# K210Module.net
KiCad netlist of a schematic drawn in Altium Designer
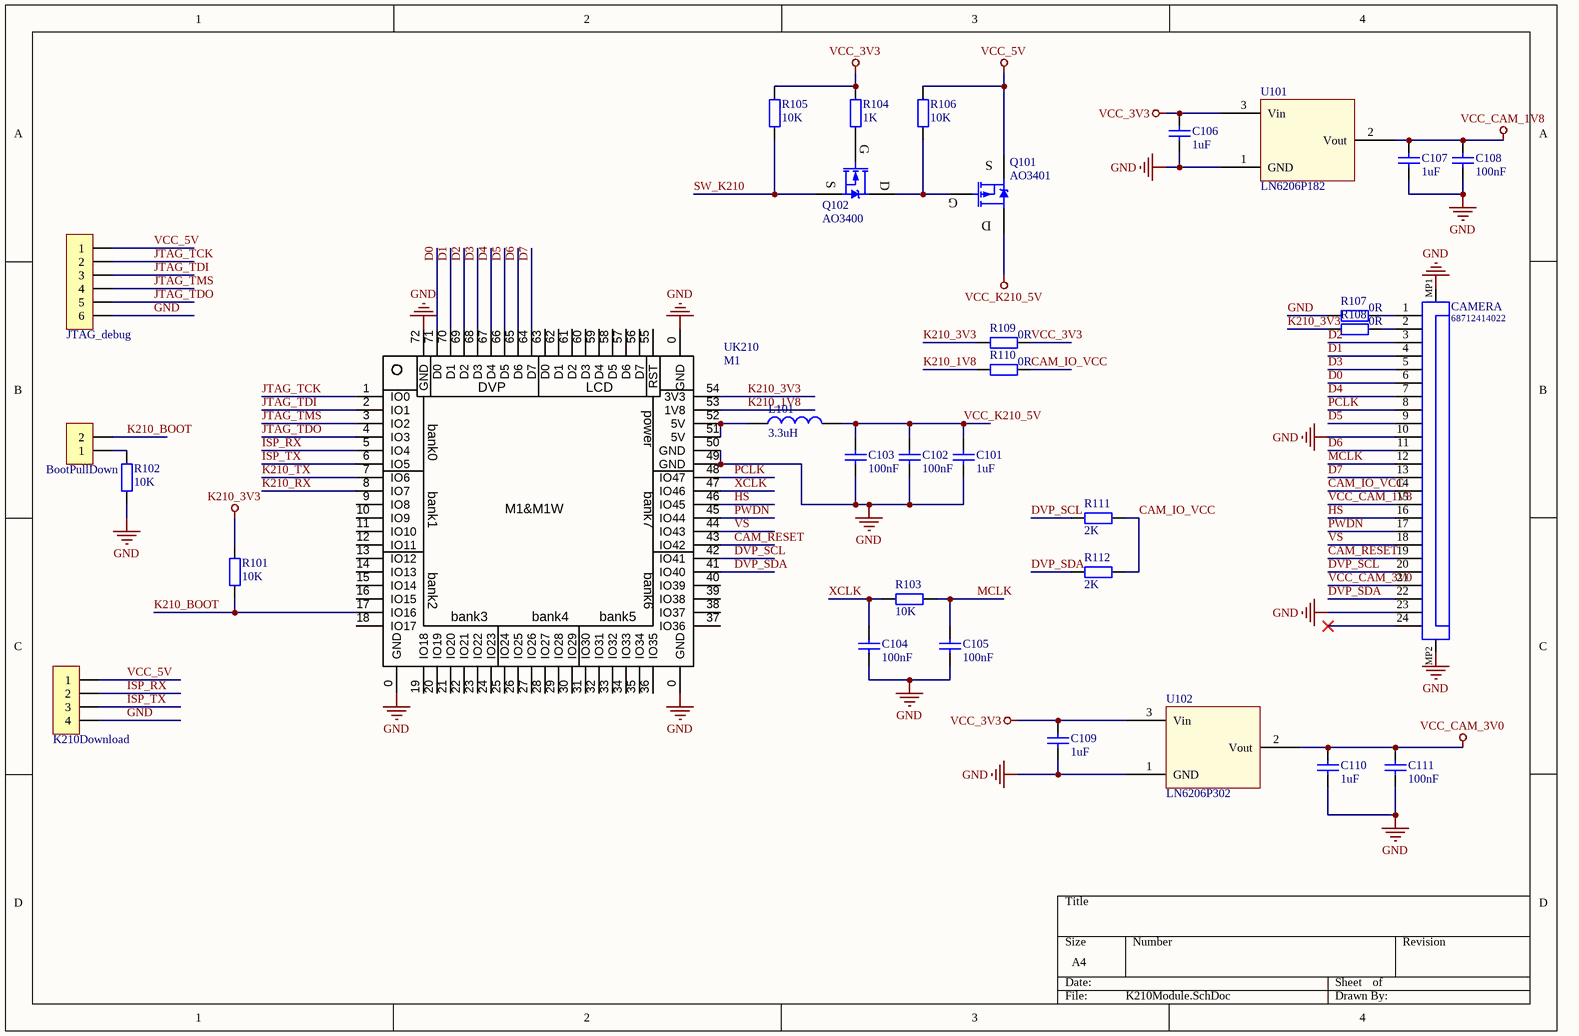
[diagram p0: K210Module.SchDoc]

(export (version "E")
  (design (tool "Eeschema 10.0.6"))
  (components
    (comp (ref "BootPullDown")
      (value "HDR-1X2")
      (footprint "HDR2.54-LI-2P")
      (description "2P接插件")
      (libsource (lib "5.5 - 2.54mm连接器(KF2EDGK_XH2.54_2.54排针排母)") (part "Header 2"))
    )
    (comp (ref "C101")
      (value "1uF")
      (footprint "C0603_L")
      (description "贴片电容/MLCC电容")
      (libsource (lib "0.1 - 电阻-电容-电感-晶振-晶体-磁珠-电位器-法拉电容-馈通电容") (part "C"))
    )
    (comp (ref "C102")
      (value "100nF")
      (footprint "C0603_L")
      (description "贴片电容/MLCC电容")
      (libsource (lib "0.1 - 电阻-电容-电感-晶振-晶体-磁珠-电位器-法拉电容-馈通电容") (part "C"))
    )
    (comp (ref "C103")
      (value "100nF")
      (footprint "C0603_L")
      (description "贴片电容/MLCC电容")
      (libsource (lib "0.1 - 电阻-电容-电感-晶振-晶体-磁珠-电位器-法拉电容-馈通电容") (part "C"))
    )
    (comp (ref "C104")
      (value "100nF")
      (footprint "C0603_L")
      (description "贴片电容/MLCC电容")
      (libsource (lib "0.1 - 电阻-电容-电感-晶振-晶体-磁珠-电位器-法拉电容-馈通电容") (part "C"))
    )
    (comp (ref "C105")
      (value "100nF")
      (footprint "C0603_L")
      (description "贴片电容/MLCC电容")
      (libsource (lib "0.1 - 电阻-电容-电感-晶振-晶体-磁珠-电位器-法拉电容-馈通电容") (part "C"))
    )
    (comp (ref "C106")
      (value "1uF")
      (footprint "C0603_L")
      (description "贴片电容/MLCC电容")
      (libsource (lib "0.1 - 电阻-电容-电感-晶振-晶体-磁珠-电位器-法拉电容-馈通电容") (part "C"))
    )
    (comp (ref "C107")
      (value "1uF")
      (footprint "C0603_L")
      (description "贴片电容/MLCC电容")
      (libsource (lib "0.1 - 电阻-电容-电感-晶振-晶体-磁珠-电位器-法拉电容-馈通电容") (part "C"))
    )
    (comp (ref "C108")
      (value "100nF")
      (footprint "C0603_L")
      (description "贴片电容/MLCC电容")
      (libsource (lib "0.1 - 电阻-电容-电感-晶振-晶体-磁珠-电位器-法拉电容-馈通电容") (part "C"))
    )
    (comp (ref "C109")
      (value "1uF")
      (footprint "C0603_L")
      (description "贴片电容/MLCC电容")
      (libsource (lib "0.1 - 电阻-电容-电感-晶振-晶体-磁珠-电位器-法拉电容-馈通电容") (part "C"))
    )
    (comp (ref "C110")
      (value "1uF")
      (footprint "C0603_L")
      (description "贴片电容/MLCC电容")
      (libsource (lib "0.1 - 电阻-电容-电感-晶振-晶体-磁珠-电位器-法拉电容-馈通电容") (part "C"))
    )
    (comp (ref "C111")
      (value "100nF")
      (footprint "C0603_L")
      (description "贴片电容/MLCC电容")
      (libsource (lib "0.1 - 电阻-电容-电感-晶振-晶体-磁珠-电位器-法拉电容-馈通电容") (part "C"))
    )
    (comp (ref "CAMERA")
      (value "68712414022")
      (footprint "68712414022")
      (description "SMT ZIF Connectors WR-FPC, Horizontal, Top Contact, pitch 0.5 mm, 24 pins")
      (fields (field (name "MANUFACTURER") "Wurth Elektronik") (field (name "PUBLISHER") "WurthElektronik"))
      (libsource (lib "Altium Content Vault") (part "WE-6871241XXX22-24"))
    )
    (comp (ref "JTAG_debug")
      (value "HDR-1X6")
      (footprint "XH2.54-LI-6P")
      (description "6P接插件")
      (libsource (lib "5.5 - 2.54mm连接器(KF2EDGK_XH2.54_2.54排针排母)") (part "Header 6"))
    )
    (comp (ref "K210Download")
      (value "HDR-1X4")
      (footprint "XH2.54-LI-4P")
      (description "4P接插件")
      (libsource (lib "5.5 - 2.54mm连接器(KF2EDGK_XH2.54_2.54排针排母)") (part "Header 4"))
    )
    (comp (ref "L101")
      (value "3.3uH")
      (footprint "L0805")
      (description "贴片小功率电感")
      (libsource (lib "0.1 - 电阻-电容-电感-晶振-晶体-磁珠-电位器-法拉电容-馈通电容") (part "L"))
    )
    (comp (ref "Q101")
      (value "AO3401")
      (footprint "SOT23-3N")
      (description "P沟道 30V/4.2A")
      (libsource (lib "0.4 - 三极管-场效应管-可控硅") (part "AO3401"))
    )
    (comp (ref "Q102")
      (value "AO3400")
      (footprint "SOT23-3N")
      (description "N沟道 30V/4.2A")
      (libsource (lib "0.4 - 三极管-场效应管-可控硅") (part "AO3400"))
    )
    (comp (ref "R101")
      (value "10K")
      (footprint "R0603_L")
      (description "贴片电阻")
      (libsource (lib "0.1 - 电阻-电容-电感-晶振-晶体-磁珠-电位器-法拉电容-馈通电容") (part "R"))
    )
    (comp (ref "R102")
      (value "10K")
      (footprint "R0603_L")
      (description "贴片电阻")
      (libsource (lib "0.1 - 电阻-电容-电感-晶振-晶体-磁珠-电位器-法拉电容-馈通电容") (part "R"))
    )
    (comp (ref "R103")
      (value "10K")
      (footprint "R0603_L")
      (description "贴片电阻")
      (libsource (lib "0.1 - 电阻-电容-电感-晶振-晶体-磁珠-电位器-法拉电容-馈通电容") (part "R"))
    )
    (comp (ref "R104")
      (value "1K")
      (footprint "R0603_L")
      (description "贴片电阻")
      (libsource (lib "0.1 - 电阻-电容-电感-晶振-晶体-磁珠-电位器-法拉电容-馈通电容") (part "R"))
    )
    (comp (ref "R105")
      (value "10K")
      (footprint "R0603_L")
      (description "贴片电阻")
      (libsource (lib "0.1 - 电阻-电容-电感-晶振-晶体-磁珠-电位器-法拉电容-馈通电容") (part "R"))
    )
    (comp (ref "R106")
      (value "10K")
      (footprint "R0603_L")
      (description "贴片电阻")
      (libsource (lib "0.1 - 电阻-电容-电感-晶振-晶体-磁珠-电位器-法拉电容-馈通电容") (part "R"))
    )
    (comp (ref "R107")
      (value "0R")
      (footprint "R0603_L")
      (description "贴片电阻")
      (libsource (lib "0.1 - 电阻-电容-电感-晶振-晶体-磁珠-电位器-法拉电容-馈通电容") (part "R"))
    )
    (comp (ref "R108")
      (value "0R")
      (footprint "R0603_L")
      (description "贴片电阻")
      (libsource (lib "0.1 - 电阻-电容-电感-晶振-晶体-磁珠-电位器-法拉电容-馈通电容") (part "R"))
    )
    (comp (ref "R109")
      (value "0R")
      (footprint "R0603_L")
      (description "贴片电阻")
      (libsource (lib "0.1 - 电阻-电容-电感-晶振-晶体-磁珠-电位器-法拉电容-馈通电容") (part "R"))
    )
    (comp (ref "R110")
      (value "0R")
      (footprint "R0603_L")
      (description "贴片电阻")
      (libsource (lib "0.1 - 电阻-电容-电感-晶振-晶体-磁珠-电位器-法拉电容-馈通电容") (part "R"))
    )
    (comp (ref "R111")
      (value "2K")
      (footprint "R0603_L")
      (description "贴片电阻")
      (libsource (lib "0.1 - 电阻-电容-电感-晶振-晶体-磁珠-电位器-法拉电容-馈通电容") (part "R"))
    )
    (comp (ref "R112")
      (value "2K")
      (footprint "R0603_L")
      (description "贴片电阻")
      (libsource (lib "0.1 - 电阻-电容-电感-晶振-晶体-磁珠-电位器-法拉电容-馈通电容") (part "R"))
    )
    (comp (ref "U101")
      (value "LN6206P182")
      (footprint "SOT23-3L")
      (libsource (lib "calorieScale") (part "LN6206P*"))
    )
    (comp (ref "U102")
      (value "LN6206P302")
      (footprint "SOT23-3L")
      (libsource (lib "calorieScale") (part "LN6206P*"))
    )
    (comp (ref "UK210") (value "M1") (footprint "M1") (libsource (lib "M1&M1W") (part "M1")))
  )
  (nets
    (net (code "1") (name "/CAM_IO_VCC") (class "Default")
      (node (ref "CAMERA") (pin "14") (pinfunction "14_14") (pintype "passive"))
      (node (ref "R110") (pin "1") (pinfunction "1_1") (pintype "passive"))
      (node (ref "R111") (pin "2") (pinfunction "2_2") (pintype "passive"))
      (node (ref "R112") (pin "2") (pinfunction "2_2") (pintype "passive"))
    )
    (net (code "2") (name "/CAM_RESET") (class "Default")
      (node (ref "CAMERA") (pin "19") (pinfunction "19_19") (pintype "passive"))
      (node (ref "UK210") (pin "43") (pinfunction "IO42_43") (pintype "passive"))
    )
    (net (code "3") (name "/D0") (class "Default")
      (node (ref "CAMERA") (pin "6") (pinfunction "6_6") (pintype "passive"))
      (node (ref "UK210") (pin "71") (pinfunction "D0_71") (pintype "passive"))
    )
    (net (code "4") (name "/D1") (class "Default")
      (node (ref "CAMERA") (pin "4") (pinfunction "4_4") (pintype "passive"))
      (node (ref "UK210") (pin "70") (pinfunction "D1_70") (pintype "passive"))
    )
    (net (code "5") (name "/D2") (class "Default")
      (node (ref "CAMERA") (pin "3") (pinfunction "3_3") (pintype "passive"))
      (node (ref "UK210") (pin "69") (pinfunction "D2_69") (pintype "passive"))
    )
    (net (code "6") (name "/D3") (class "Default")
      (node (ref "CAMERA") (pin "5") (pinfunction "5_5") (pintype "passive"))
      (node (ref "UK210") (pin "68") (pinfunction "D3_68") (pintype "passive"))
    )
    (net (code "7") (name "/D4") (class "Default")
      (node (ref "CAMERA") (pin "7") (pinfunction "7_7") (pintype "passive"))
      (node (ref "UK210") (pin "67") (pinfunction "D4_67") (pintype "passive"))
    )
    (net (code "8") (name "/D5") (class "Default")
      (node (ref "CAMERA") (pin "9") (pinfunction "9_9") (pintype "passive"))
      (node (ref "UK210") (pin "66") (pinfunction "D5_66") (pintype "passive"))
    )
    (net (code "9") (name "/D6") (class "Default")
      (node (ref "CAMERA") (pin "11") (pinfunction "11_11") (pintype "passive"))
      (node (ref "UK210") (pin "65") (pinfunction "D6_65") (pintype "passive"))
    )
    (net (code "10") (name "/D7") (class "Default")
      (node (ref "CAMERA") (pin "13") (pinfunction "13_13") (pintype "passive"))
      (node (ref "UK210") (pin "64") (pinfunction "D7_64") (pintype "passive"))
    )
    (net (code "11") (name "/DVP_SCL") (class "Default")
      (node (ref "CAMERA") (pin "20") (pinfunction "20_20") (pintype "passive"))
      (node (ref "R111") (pin "1") (pinfunction "1_1") (pintype "passive"))
      (node (ref "UK210") (pin "42") (pinfunction "IO41_42") (pintype "passive"))
    )
    (net (code "12") (name "/DVP_SDA") (class "Default")
      (node (ref "CAMERA") (pin "22") (pinfunction "22_22") (pintype "passive"))
      (node (ref "R112") (pin "1") (pinfunction "1_1") (pintype "passive"))
      (node (ref "UK210") (pin "41") (pinfunction "IO40_41") (pintype "passive"))
    )
    (net (code "13") (name "/HS") (class "Default")
      (node (ref "CAMERA") (pin "16") (pinfunction "16_16") (pintype "passive"))
      (node (ref "UK210") (pin "46") (pinfunction "IO45_46") (pintype "passive"))
    )
    (net (code "14") (name "/ISP_RX") (class "Default")
      (node (ref "K210Download") (pin "2") (pinfunction "2_2") (pintype "passive"))
      (node (ref "UK210") (pin "5") (pinfunction "IO4_5") (pintype "passive"))
    )
    (net (code "15") (name "/ISP_TX") (class "Default")
      (node (ref "K210Download") (pin "3") (pinfunction "3_3") (pintype "passive"))
      (node (ref "UK210") (pin "6") (pinfunction "IO5_6") (pintype "passive"))
    )
    (net (code "16") (name "/JTAG_TCK") (class "Default")
      (node (ref "JTAG_debug") (pin "2") (pinfunction "2_2") (pintype "passive"))
      (node (ref "UK210") (pin "1") (pinfunction "IO0_1") (pintype "passive"))
    )
    (net (code "17") (name "/JTAG_TDI") (class "Default")
      (node (ref "JTAG_debug") (pin "3") (pinfunction "3_3") (pintype "passive"))
      (node (ref "UK210") (pin "2") (pinfunction "IO1_2") (pintype "passive"))
    )
    (net (code "18") (name "/JTAG_TDO") (class "Default")
      (node (ref "JTAG_debug") (pin "5") (pinfunction "5_5") (pintype "passive"))
      (node (ref "UK210") (pin "4") (pinfunction "IO3_4") (pintype "passive"))
    )
    (net (code "19") (name "/JTAG_TMS") (class "Default")
      (node (ref "JTAG_debug") (pin "4") (pinfunction "4_4") (pintype "passive"))
      (node (ref "UK210") (pin "3") (pinfunction "IO2_3") (pintype "passive"))
    )
    (net (code "20") (name "/K210_1V8") (class "Default")
      (node (ref "R110") (pin "2") (pinfunction "2_2") (pintype "passive"))
      (node (ref "UK210") (pin "53") (pinfunction "1V8_53") (pintype "passive"))
    )
    (net (code "21") (name "/K210_BOOT") (class "Default")
      (node (ref "BootPullDown") (pin "2") (pinfunction "2_2") (pintype "passive"))
      (node (ref "R101") (pin "1") (pinfunction "1_1") (pintype "passive"))
      (node (ref "UK210") (pin "17") (pinfunction "IO16_17") (pintype "passive"))
    )
    (net (code "22") (name "/K210_RX") (class "Default")
      (node (ref "UK210") (pin "8") (pinfunction "IO7_8") (pintype "passive"))
    )
    (net (code "23") (name "/K210_TX") (class "Default")
      (node (ref "UK210") (pin "7") (pinfunction "IO6_7") (pintype "passive"))
    )
    (net (code "24") (name "/MCLK") (class "Default")
      (node (ref "C105") (pin "2") (pinfunction "2_2") (pintype "passive"))
      (node (ref "CAMERA") (pin "12") (pinfunction "12_12") (pintype "passive"))
      (node (ref "R103") (pin "2") (pinfunction "2_2") (pintype "passive"))
    )
    (net (code "25") (name "/PCLK") (class "Default")
      (node (ref "CAMERA") (pin "8") (pinfunction "8_8") (pintype "passive"))
      (node (ref "UK210") (pin "48") (pinfunction "IO47_48") (pintype "passive"))
    )
    (net (code "26") (name "/PWDN") (class "Default")
      (node (ref "CAMERA") (pin "17") (pinfunction "17_17") (pintype "passive"))
      (node (ref "UK210") (pin "45") (pinfunction "IO44_45") (pintype "passive"))
    )
    (net (code "27") (name "/SW_K210") (class "Default")
      (node (ref "Q102") (pin "2") (pinfunction "S_2") (pintype "passive"))
      (node (ref "R105") (pin "1") (pinfunction "1_1") (pintype "passive"))
    )
    (net (code "28") (name "/VS") (class "Default")
      (node (ref "CAMERA") (pin "18") (pinfunction "18_18") (pintype "passive"))
      (node (ref "UK210") (pin "44") (pinfunction "IO43_44") (pintype "passive"))
    )
    (net (code "29") (name "/XCLK") (class "Default")
      (node (ref "C104") (pin "2") (pinfunction "2_2") (pintype "passive"))
      (node (ref "R103") (pin "1") (pinfunction "1_1") (pintype "passive"))
      (node (ref "UK210") (pin "47") (pinfunction "IO46_47") (pintype "passive"))
    )
    (net (code "30") (name "GND") (class "Default")
      (node (ref "C101") (pin "1") (pinfunction "1_1") (pintype "passive"))
      (node (ref "C102") (pin "1") (pinfunction "1_1") (pintype "passive"))
      (node (ref "C103") (pin "1") (pinfunction "1_1") (pintype "passive"))
      (node (ref "C104") (pin "1") (pinfunction "1_1") (pintype "passive"))
      (node (ref "C105") (pin "1") (pinfunction "1_1") (pintype "passive"))
      (node (ref "C106") (pin "1") (pinfunction "1_1") (pintype "passive"))
      (node (ref "C107") (pin "1") (pinfunction "1_1") (pintype "passive"))
      (node (ref "C108") (pin "1") (pinfunction "1_1") (pintype "passive"))
      (node (ref "C109") (pin "1") (pinfunction "1_1") (pintype "passive"))
      (node (ref "C110") (pin "1") (pinfunction "1_1") (pintype "passive"))
      (node (ref "C111") (pin "1") (pinfunction "1_1") (pintype "passive"))
      (node (ref "CAMERA") (pin "10") (pinfunction "10_10") (pintype "passive"))
      (node (ref "CAMERA") (pin "23") (pinfunction "23_23") (pintype "passive"))
      (node (ref "CAMERA") (pin "MP1") (pinfunction "MP1_MP1") (pintype "passive"))
      (node (ref "CAMERA") (pin "MP2") (pinfunction "MP2_MP2") (pintype "passive"))
      (node (ref "JTAG_debug") (pin "6") (pinfunction "6_6") (pintype "passive"))
      (node (ref "K210Download") (pin "4") (pinfunction "4_4") (pintype "passive"))
      (node (ref "R102") (pin "2") (pinfunction "2_2") (pintype "passive"))
      (node (ref "R107") (pin "2") (pinfunction "2_2") (pintype "passive"))
      (node (ref "U101") (pin "1") (pinfunction "GND_1") (pintype "passive"))
      (node (ref "U102") (pin "1") (pinfunction "GND_1") (pintype "passive"))
      (node (ref "UK210") (pin "0") (pinfunction "GND_0") (pintype "passive"))
      (node (ref "UK210") (pin "49") (pinfunction "GND_49") (pintype "passive"))
      (node (ref "UK210") (pin "50") (pinfunction "GND_50") (pintype "passive"))
      (node (ref "UK210") (pin "72") (pinfunction "GND_72") (pintype "passive"))
    )
    (net (code "31") (name "K210_3V3") (class "Default")
      (node (ref "R101") (pin "2") (pinfunction "2_2") (pintype "passive"))
      (node (ref "R108") (pin "2") (pinfunction "2_2") (pintype "passive"))
      (node (ref "R109") (pin "2") (pinfunction "2_2") (pintype "passive"))
      (node (ref "UK210") (pin "54") (pinfunction "3V3_54") (pintype "passive"))
    )
    (net (code "32") (name "Net-(BootPullDown-Pad1)") (class "Default")
      (node (ref "BootPullDown") (pin "1") (pinfunction "1_1") (pintype "passive"))
      (node (ref "R102") (pin "1") (pinfunction "1_1") (pintype "passive"))
    )
    (net (code "33") (name "Net-(CAMERA-Pad1)") (class "Default")
      (node (ref "CAMERA") (pin "1") (pinfunction "1_1") (pintype "passive"))
      (node (ref "R107") (pin "1") (pinfunction "1_1") (pintype "passive"))
    )
    (net (code "34") (name "Net-(CAMERA-Pad2)") (class "Default")
      (node (ref "CAMERA") (pin "2") (pinfunction "2_2") (pintype "passive"))
      (node (ref "R108") (pin "1") (pinfunction "1_1") (pintype "passive"))
    )
    (net (code "35") (name "Net-(L101-Pad1)") (class "Default")
      (node (ref "L101") (pin "1") (pinfunction "1_1") (pintype "passive"))
      (node (ref "UK210") (pin "51") (pinfunction "5V_51") (pintype "passive"))
      (node (ref "UK210") (pin "52") (pinfunction "5V_52") (pintype "passive"))
    )
    (net (code "36") (name "Net-(Q101-G)") (class "Default")
      (node (ref "Q101") (pin "1") (pinfunction "G_1") (pintype "passive"))
      (node (ref "Q102") (pin "3") (pinfunction "D_3") (pintype "passive"))
      (node (ref "R106") (pin "1") (pinfunction "1_1") (pintype "passive"))
    )
    (net (code "37") (name "Net-(Q102-G)") (class "Default")
      (node (ref "Q102") (pin "1") (pinfunction "G_1") (pintype "passive"))
      (node (ref "R104") (pin "1") (pinfunction "1_1") (pintype "passive"))
    )
    (net (code "38") (name "VCC_3V3") (class "Default")
      (node (ref "C106") (pin "2") (pinfunction "2_2") (pintype "passive"))
      (node (ref "C109") (pin "2") (pinfunction "2_2") (pintype "passive"))
      (node (ref "R104") (pin "2") (pinfunction "2_2") (pintype "passive"))
      (node (ref "R105") (pin "2") (pinfunction "2_2") (pintype "passive"))
      (node (ref "R109") (pin "1") (pinfunction "1_1") (pintype "passive"))
      (node (ref "U101") (pin "3") (pinfunction "Vin_3") (pintype "passive"))
      (node (ref "U102") (pin "3") (pinfunction "Vin_3") (pintype "passive"))
    )
    (net (code "39") (name "VCC_5V") (class "Default")
      (node (ref "JTAG_debug") (pin "1") (pinfunction "1_1") (pintype "passive"))
      (node (ref "K210Download") (pin "1") (pinfunction "1_1") (pintype "passive"))
      (node (ref "Q101") (pin "2") (pinfunction "S_2") (pintype "passive"))
      (node (ref "R106") (pin "2") (pinfunction "2_2") (pintype "passive"))
    )
    (net (code "40") (name "VCC_CAM_1V8") (class "Default")
      (node (ref "C107") (pin "2") (pinfunction "2_2") (pintype "passive"))
      (node (ref "C108") (pin "2") (pinfunction "2_2") (pintype "passive"))
      (node (ref "CAMERA") (pin "15") (pinfunction "15_15") (pintype "passive"))
      (node (ref "U101") (pin "2") (pinfunction "Vout_2") (pintype "passive"))
    )
    (net (code "41") (name "VCC_CAM_3V0") (class "Default")
      (node (ref "C110") (pin "2") (pinfunction "2_2") (pintype "passive"))
      (node (ref "C111") (pin "2") (pinfunction "2_2") (pintype "passive"))
      (node (ref "CAMERA") (pin "21") (pinfunction "21_21") (pintype "passive"))
      (node (ref "U102") (pin "2") (pinfunction "Vout_2") (pintype "passive"))
    )
    (net (code "42") (name "VCC_K210_5V") (class "Default")
      (node (ref "C101") (pin "2") (pinfunction "2_2") (pintype "passive"))
      (node (ref "C102") (pin "2") (pinfunction "2_2") (pintype "passive"))
      (node (ref "C103") (pin "2") (pinfunction "2_2") (pintype "passive"))
      (node (ref "L101") (pin "2") (pinfunction "2_2") (pintype "passive"))
      (node (ref "Q101") (pin "3") (pinfunction "D_3") (pintype "passive"))
    )
    (net (code "43") (name "unconnected-(CAMERA-Pad24)") (class "Default")
      (node (ref "CAMERA") (pin "24") (pinfunction "24_24") (pintype "passive+no_connect"))
    )
    (net (code "44") (name "unconnected-(UK210-D0-Pad63)") (class "Default")
      (node (ref "UK210") (pin "63") (pinfunction "D0_63") (pintype "passive"))
    )
    (net (code "45") (name "unconnected-(UK210-D1-Pad62)") (class "Default")
      (node (ref "UK210") (pin "62") (pinfunction "D1_62") (pintype "passive"))
    )
    (net (code "46") (name "unconnected-(UK210-D2-Pad61)") (class "Default")
      (node (ref "UK210") (pin "61") (pinfunction "D2_61") (pintype "passive"))
    )
    (net (code "47") (name "unconnected-(UK210-D3-Pad60)") (class "Default")
      (node (ref "UK210") (pin "60") (pinfunction "D3_60") (pintype "passive"))
    )
    (net (code "48") (name "unconnected-(UK210-D4-Pad59)") (class "Default")
      (node (ref "UK210") (pin "59") (pinfunction "D4_59") (pintype "passive"))
    )
    (net (code "49") (name "unconnected-(UK210-D5-Pad58)") (class "Default")
      (node (ref "UK210") (pin "58") (pinfunction "D5_58") (pintype "passive"))
    )
    (net (code "50") (name "unconnected-(UK210-D6-Pad57)") (class "Default")
      (node (ref "UK210") (pin "57") (pinfunction "D6_57") (pintype "passive"))
    )
    (net (code "51") (name "unconnected-(UK210-D7-Pad56)") (class "Default")
      (node (ref "UK210") (pin "56") (pinfunction "D7_56") (pintype "passive"))
    )
    (net (code "52") (name "unconnected-(UK210-IO8-Pad9)") (class "Default")
      (node (ref "UK210") (pin "9") (pinfunction "IO8_9") (pintype "passive"))
    )
    (net (code "53") (name "unconnected-(UK210-IO9-Pad10)") (class "Default")
      (node (ref "UK210") (pin "10") (pinfunction "IO9_10") (pintype "passive"))
    )
    (net (code "54") (name "unconnected-(UK210-IO10-Pad11)") (class "Default")
      (node (ref "UK210") (pin "11") (pinfunction "IO10_11") (pintype "passive"))
    )
    (net (code "55") (name "unconnected-(UK210-IO11-Pad12)") (class "Default")
      (node (ref "UK210") (pin "12") (pinfunction "IO11_12") (pintype "passive"))
    )
    (net (code "56") (name "unconnected-(UK210-IO12-Pad13)") (class "Default")
      (node (ref "UK210") (pin "13") (pinfunction "IO12_13") (pintype "passive"))
    )
    (net (code "57") (name "unconnected-(UK210-IO13-Pad14)") (class "Default")
      (node (ref "UK210") (pin "14") (pinfunction "IO13_14") (pintype "passive"))
    )
    (net (code "58") (name "unconnected-(UK210-IO14-Pad15)") (class "Default")
      (node (ref "UK210") (pin "15") (pinfunction "IO14_15") (pintype "passive"))
    )
    (net (code "59") (name "unconnected-(UK210-IO15-Pad16)") (class "Default")
      (node (ref "UK210") (pin "16") (pinfunction "IO15_16") (pintype "passive"))
    )
    (net (code "60") (name "unconnected-(UK210-IO17-Pad18)") (class "Default")
      (node (ref "UK210") (pin "18") (pinfunction "IO17_18") (pintype "passive"))
    )
    (net (code "61") (name "unconnected-(UK210-IO18-Pad19)") (class "Default")
      (node (ref "UK210") (pin "19") (pinfunction "IO18_19") (pintype "passive"))
    )
    (net (code "62") (name "unconnected-(UK210-IO19-Pad20)") (class "Default")
      (node (ref "UK210") (pin "20") (pinfunction "IO19_20") (pintype "passive"))
    )
    (net (code "63") (name "unconnected-(UK210-IO20-Pad21)") (class "Default")
      (node (ref "UK210") (pin "21") (pinfunction "IO20_21") (pintype "passive"))
    )
    (net (code "64") (name "unconnected-(UK210-IO21-Pad22)") (class "Default")
      (node (ref "UK210") (pin "22") (pinfunction "IO21_22") (pintype "passive"))
    )
    (net (code "65") (name "unconnected-(UK210-IO22-Pad23)") (class "Default")
      (node (ref "UK210") (pin "23") (pinfunction "IO22_23") (pintype "passive"))
    )
    (net (code "66") (name "unconnected-(UK210-IO23-Pad24)") (class "Default")
      (node (ref "UK210") (pin "24") (pinfunction "IO23_24") (pintype "passive"))
    )
    (net (code "67") (name "unconnected-(UK210-IO24-Pad25)") (class "Default")
      (node (ref "UK210") (pin "25") (pinfunction "IO24_25") (pintype "passive"))
    )
    (net (code "68") (name "unconnected-(UK210-IO25-Pad26)") (class "Default")
      (node (ref "UK210") (pin "26") (pinfunction "IO25_26") (pintype "passive"))
    )
    (net (code "69") (name "unconnected-(UK210-IO26-Pad27)") (class "Default")
      (node (ref "UK210") (pin "27") (pinfunction "IO26_27") (pintype "passive"))
    )
    (net (code "70") (name "unconnected-(UK210-IO27-Pad28)") (class "Default")
      (node (ref "UK210") (pin "28") (pinfunction "IO27_28") (pintype "passive"))
    )
    (net (code "71") (name "unconnected-(UK210-IO28-Pad29)") (class "Default")
      (node (ref "UK210") (pin "29") (pinfunction "IO28_29") (pintype "passive"))
    )
    (net (code "72") (name "unconnected-(UK210-IO29-Pad30)") (class "Default")
      (node (ref "UK210") (pin "30") (pinfunction "IO29_30") (pintype "passive"))
    )
    (net (code "73") (name "unconnected-(UK210-IO30-Pad31)") (class "Default")
      (node (ref "UK210") (pin "31") (pinfunction "IO30_31") (pintype "passive"))
    )
    (net (code "74") (name "unconnected-(UK210-IO31-Pad32)") (class "Default")
      (node (ref "UK210") (pin "32") (pinfunction "IO31_32") (pintype "passive"))
    )
    (net (code "75") (name "unconnected-(UK210-IO32-Pad33)") (class "Default")
      (node (ref "UK210") (pin "33") (pinfunction "IO32_33") (pintype "passive"))
    )
    (net (code "76") (name "unconnected-(UK210-IO33-Pad34)") (class "Default")
      (node (ref "UK210") (pin "34") (pinfunction "IO33_34") (pintype "passive"))
    )
    (net (code "77") (name "unconnected-(UK210-IO34-Pad35)") (class "Default")
      (node (ref "UK210") (pin "35") (pinfunction "IO34_35") (pintype "passive"))
    )
    (net (code "78") (name "unconnected-(UK210-IO35-Pad36)") (class "Default")
      (node (ref "UK210") (pin "36") (pinfunction "IO35_36") (pintype "passive"))
    )
    (net (code "79") (name "unconnected-(UK210-IO36-Pad37)") (class "Default")
      (node (ref "UK210") (pin "37") (pinfunction "IO36_37") (pintype "passive"))
    )
    (net (code "80") (name "unconnected-(UK210-IO37-Pad38)") (class "Default")
      (node (ref "UK210") (pin "38") (pinfunction "IO37_38") (pintype "passive"))
    )
    (net (code "81") (name "unconnected-(UK210-IO38-Pad39)") (class "Default")
      (node (ref "UK210") (pin "39") (pinfunction "IO38_39") (pintype "passive"))
    )
    (net (code "82") (name "unconnected-(UK210-IO39-Pad40)") (class "Default")
      (node (ref "UK210") (pin "40") (pinfunction "IO39_40") (pintype "passive"))
    )
    (net (code "83") (name "unconnected-(UK210-RST-Pad55)") (class "Default")
      (node (ref "UK210") (pin "55") (pinfunction "RST_55") (pintype "passive"))
    )
  )
)
